# utilidong-butt-mk-1_0.net
KiCad netlist of a schematic drawn in EAGLE
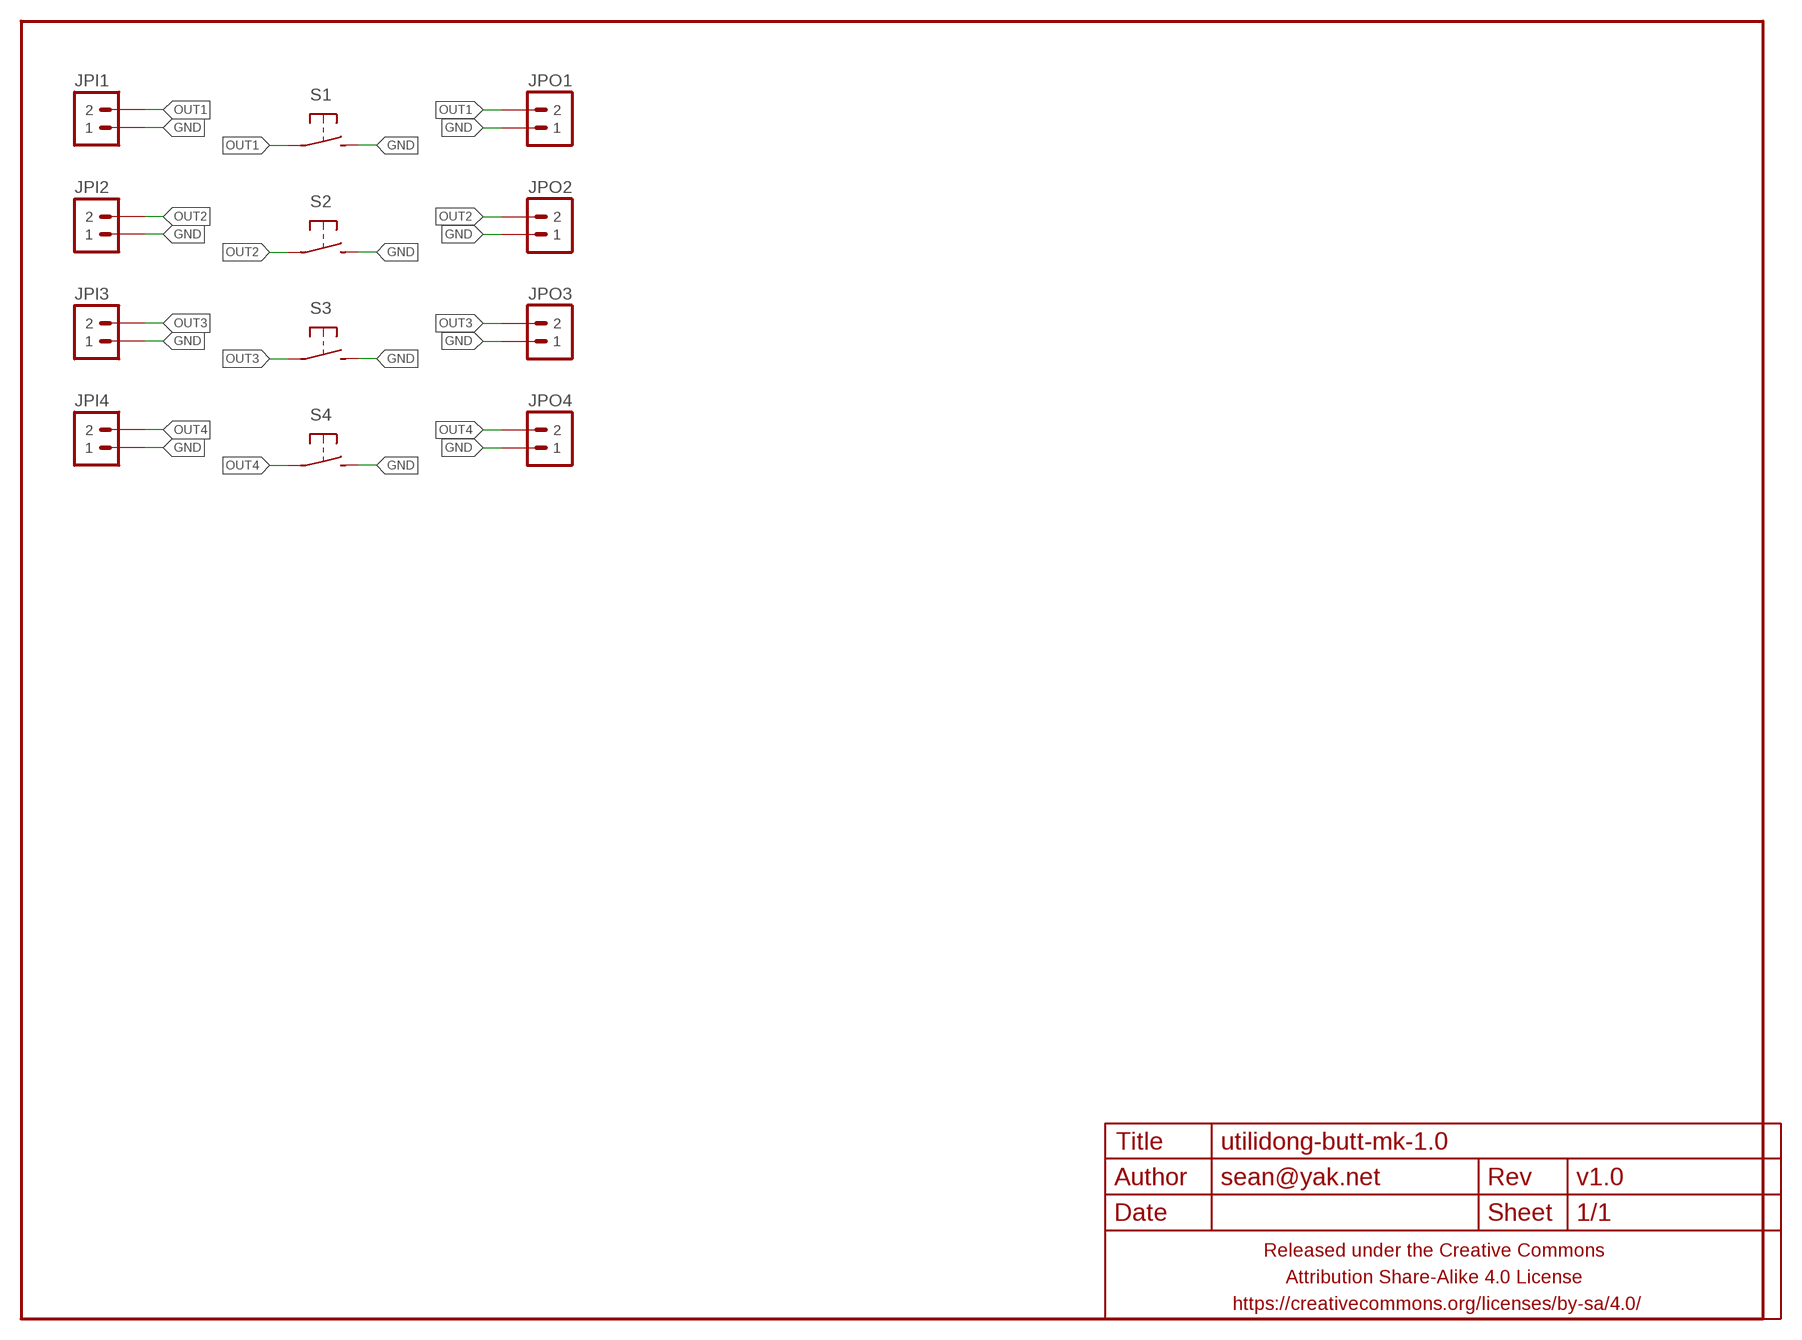
[diagram p0: schematic, sheet 1]

(export (version "E")
  (design (tool "Eeschema 10.0.6"))
  (components
    (comp (ref "FRAME1")
      (value "FRAME-LETTERNO_PACKAGE")
      (footprint "eagle-import:DUMMY")
      (fields (field (name "DESIGNER") "sean@yak.net") (field (name "VERSION") "v1.0"))
      (libsource (lib "eagle-import") (part "FRAME-LETTERNO_PACKAGE"))
    )
    (comp (ref "JPI1")
      (value "M02PTH-CENTERED")
      (footprint "eagle-import:1X02-CENTER")
      (libsource (lib "eagle-import") (part "M02PTH-CENTERED"))
    )
    (comp (ref "JPI2")
      (value "M02PTH-CENTERED")
      (footprint "eagle-import:1X02-CENTER")
      (libsource (lib "eagle-import") (part "M02PTH-CENTERED"))
    )
    (comp (ref "JPI3")
      (value "M02PTH-CENTERED")
      (footprint "eagle-import:1X02-CENTER")
      (libsource (lib "eagle-import") (part "M02PTH-CENTERED"))
    )
    (comp (ref "JPI4")
      (value "M02PTH-CENTERED")
      (footprint "eagle-import:1X02-CENTER")
      (libsource (lib "eagle-import") (part "M02PTH-CENTERED"))
    )
    (comp (ref "JPO1")
      (value "M02PTH-CENTERED")
      (footprint "eagle-import:1X02-CENTER")
      (libsource (lib "eagle-import") (part "M02PTH-CENTERED"))
    )
    (comp (ref "JPO2")
      (value "M02PTH-CENTERED")
      (footprint "eagle-import:1X02-CENTER")
      (libsource (lib "eagle-import") (part "M02PTH-CENTERED"))
    )
    (comp (ref "JPO3")
      (value "M02PTH-CENTERED")
      (footprint "eagle-import:1X02-CENTER")
      (libsource (lib "eagle-import") (part "M02PTH-CENTERED"))
    )
    (comp (ref "JPO4")
      (value "M02PTH-CENTERED")
      (footprint "eagle-import:1X02-CENTER")
      (libsource (lib "eagle-import") (part "M02PTH-CENTERED"))
    )
    (comp (ref "S1")
      (value "SPST-NO-TACT6MM-PTH-SMALL-PADS")
      (footprint "eagle-import:DTS-6-SMALL-PADS")
      (libsource (lib "eagle-import") (part "SPST-NO-TACT6MM-PTH-SMALL-PADS"))
    )
    (comp (ref "S2")
      (value "SPST-NO-TACT6MM-PTH-SMALL-PADS")
      (footprint "eagle-import:DTS-6-SMALL-PADS")
      (libsource (lib "eagle-import") (part "SPST-NO-TACT6MM-PTH-SMALL-PADS"))
    )
    (comp (ref "S3")
      (value "SPST-NO-TACT6MM-PTH-SMALL-PADS")
      (footprint "eagle-import:DTS-6-SMALL-PADS")
      (libsource (lib "eagle-import") (part "SPST-NO-TACT6MM-PTH-SMALL-PADS"))
    )
    (comp (ref "S4")
      (value "SPST-NO-TACT6MM-PTH-SMALL-PADS")
      (footprint "eagle-import:DTS-6-SMALL-PADS")
      (libsource (lib "eagle-import") (part "SPST-NO-TACT6MM-PTH-SMALL-PADS"))
    )
  )
  (nets
    (net (code "1") (name "GND") (class "Default")
      (node (ref "JPI1") (pin "1") (pinfunction "1_1") (pintype "passive"))
      (node (ref "JPI2") (pin "1") (pinfunction "1_1") (pintype "passive"))
      (node (ref "JPI3") (pin "1") (pinfunction "1_1") (pintype "passive"))
      (node (ref "JPI4") (pin "1") (pinfunction "1_1") (pintype "passive"))
      (node (ref "JPO1") (pin "1") (pinfunction "1_1") (pintype "passive"))
      (node (ref "JPO2") (pin "1") (pinfunction "1_1") (pintype "passive"))
      (node (ref "JPO3") (pin "1") (pinfunction "1_1") (pintype "passive"))
      (node (ref "JPO4") (pin "1") (pinfunction "1_1") (pintype "passive"))
      (node (ref "S1") (pin "3") (pinfunction "2_3") (pintype "passive"))
      (node (ref "S1") (pin "4") (pinfunction "2_4") (pintype "passive"))
      (node (ref "S2") (pin "3") (pinfunction "2_3") (pintype "passive"))
      (node (ref "S2") (pin "4") (pinfunction "2_4") (pintype "passive"))
      (node (ref "S3") (pin "3") (pinfunction "2_3") (pintype "passive"))
      (node (ref "S3") (pin "4") (pinfunction "2_4") (pintype "passive"))
      (node (ref "S4") (pin "3") (pinfunction "2_3") (pintype "passive"))
      (node (ref "S4") (pin "4") (pinfunction "2_4") (pintype "passive"))
    )
    (net (code "2") (name "OUT1") (class "Default")
      (node (ref "JPI1") (pin "2") (pinfunction "2_2") (pintype "passive"))
      (node (ref "JPO1") (pin "2") (pinfunction "2_2") (pintype "passive"))
      (node (ref "S1") (pin "1") (pinfunction "1_1") (pintype "passive"))
      (node (ref "S1") (pin "2") (pinfunction "1_2") (pintype "passive"))
    )
    (net (code "3") (name "OUT2") (class "Default")
      (node (ref "JPI2") (pin "2") (pinfunction "2_2") (pintype "passive"))
      (node (ref "JPO2") (pin "2") (pinfunction "2_2") (pintype "passive"))
      (node (ref "S2") (pin "1") (pinfunction "1_1") (pintype "passive"))
      (node (ref "S2") (pin "2") (pinfunction "1_2") (pintype "passive"))
    )
    (net (code "4") (name "OUT3") (class "Default")
      (node (ref "JPI3") (pin "2") (pinfunction "2_2") (pintype "passive"))
      (node (ref "JPO3") (pin "2") (pinfunction "2_2") (pintype "passive"))
      (node (ref "S3") (pin "1") (pinfunction "1_1") (pintype "passive"))
      (node (ref "S3") (pin "2") (pinfunction "1_2") (pintype "passive"))
    )
    (net (code "5") (name "OUT4") (class "Default")
      (node (ref "JPI4") (pin "2") (pinfunction "2_2") (pintype "passive"))
      (node (ref "JPO4") (pin "2") (pinfunction "2_2") (pintype "passive"))
      (node (ref "S4") (pin "1") (pinfunction "1_1") (pintype "passive"))
      (node (ref "S4") (pin "2") (pinfunction "1_2") (pintype "passive"))
    )
  )
)
